# SCH_Solder_2025-04-30.net
KiCad netlist of a schematic drawn in EasyEDA
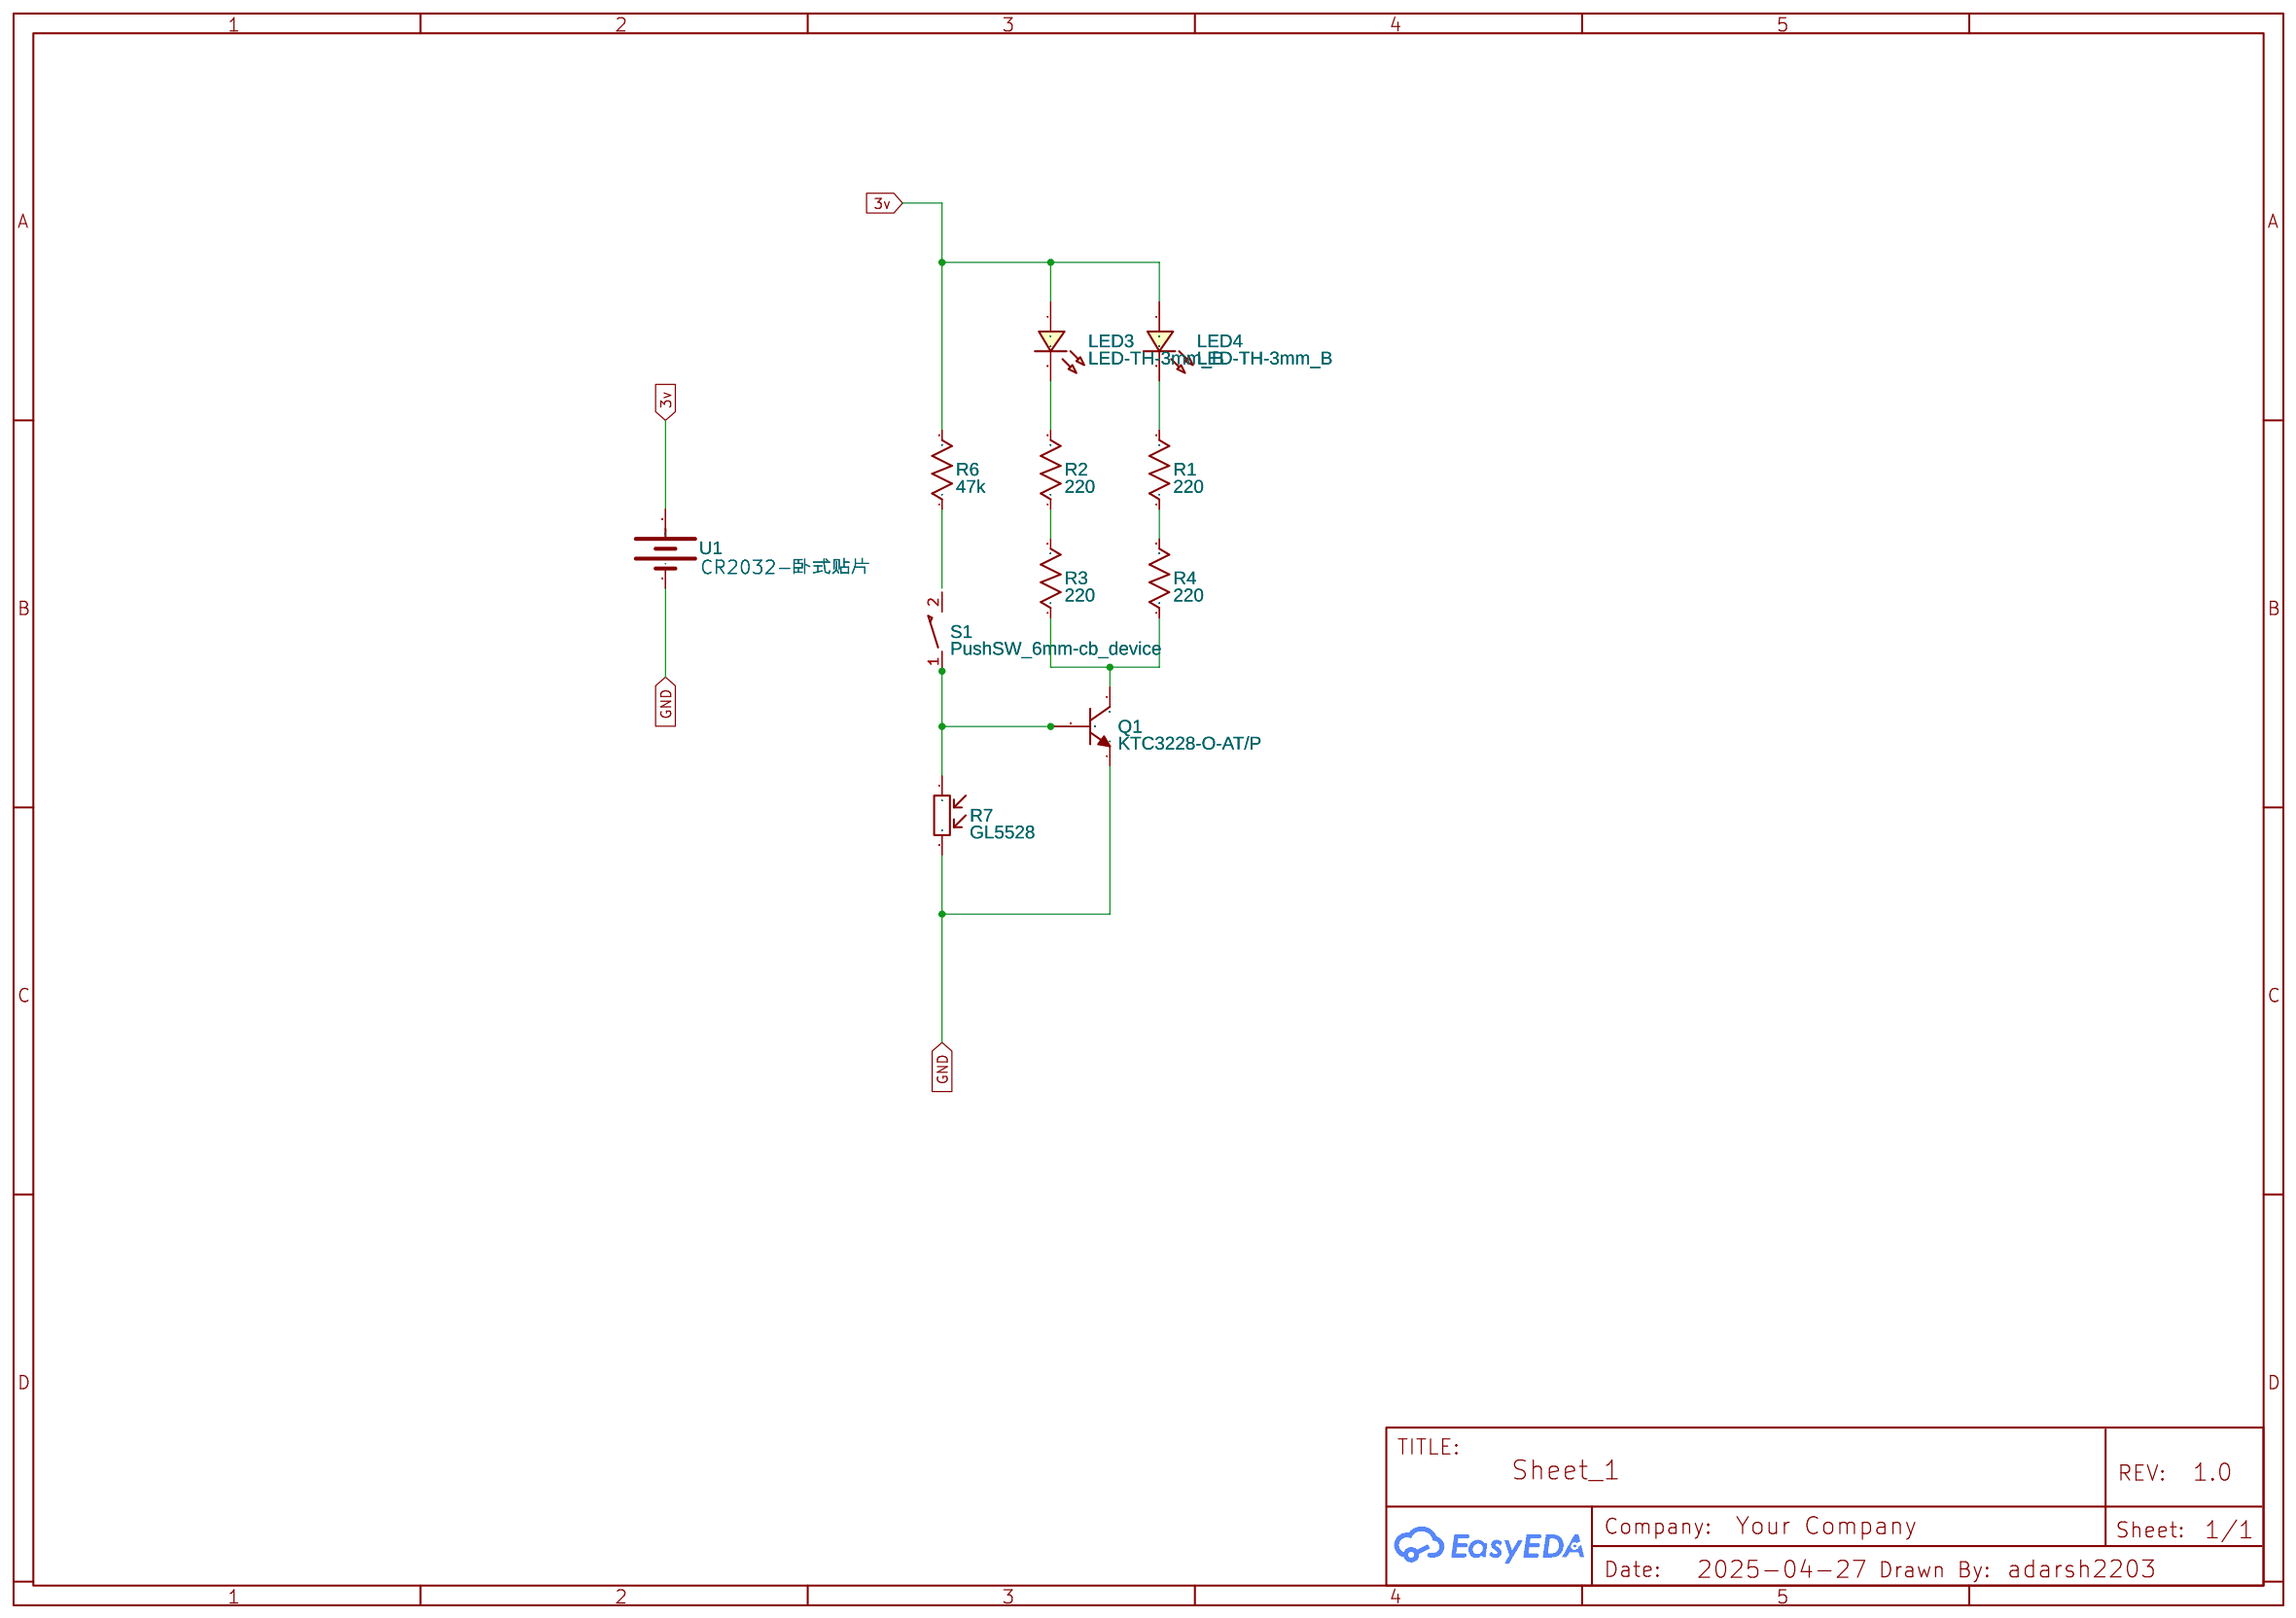
[diagram p0: schematic sheet]

(export (version "E")
  (design (tool "Eeschema 10.0.6"))
  (components
    (comp (ref "LED3")
      (value "LED-TH-3mm_B")
      (fields
        (field (name "Manufacturer Part") "204-10SUBC/S400-A4")
        (field (name "Manufacturer") "EVERLIGHT(台湾亿光)")
      )
      (libsource (lib "") (part "LED-TH-3mm_B"))
    )
    (comp (ref "LED4")
      (value "LED-TH-3mm_B")
      (fields
        (field (name "Manufacturer Part") "204-10SUBC/S400-A4")
        (field (name "Manufacturer") "EVERLIGHT(台湾亿光)")
      )
      (libsource (lib "") (part "LED-TH-3mm_B"))
    )
    (comp (ref "Q1")
      (value "KTC3228-O-AT/P")
      (fields (field (name "Manufacturer") "KEC"))
      (libsource (lib "") (part "KTC3228-O-AT/P"))
    )
    (comp (ref "R1") (value "220") (libsource (lib "") (part "R_AXIAL-0.3_US")))
    (comp (ref "R2") (value "220") (libsource (lib "") (part "R_AXIAL-0.3_US")))
    (comp (ref "R3") (value "220") (libsource (lib "") (part "R_AXIAL-0.3_US")))
    (comp (ref "R4") (value "220") (libsource (lib "") (part "R_AXIAL-0.3_US")))
    (comp (ref "R6") (value "47k") (libsource (lib "") (part "R_AXIAL-0.3_US")))
    (comp (ref "R7")
      (value "GL5528")
      (fields (field (name "Manufacturer") "森霸"))
      (libsource (lib "") (part "GL5528"))
    )
    (comp (ref "S1") (value "PushSW_6mm-cb_device") (libsource (lib "") (part "PushSW_6mm-cb_device")))
    (comp (ref "U1") (value "CR2032-卧式贴片") (libsource (lib "") (part "CR2032-卧式贴片")))
  )
  (nets
    (net (code "1") (name "3v") (class "Default")
      (node (ref "LED3") (pin "1") (pinfunction "1_1") (pintype "unspecified"))
      (node (ref "LED4") (pin "1") (pinfunction "1_1") (pintype "unspecified"))
      (node (ref "R6") (pin "2") (pinfunction "2_2") (pintype "unspecified"))
      (node (ref "U1") (pin "2") (pinfunction "+_2") (pintype "passive"))
    )
    (net (code "2") (name "GND") (class "Default")
      (node (ref "Q1") (pin "1") (pinfunction "E_1") (pintype "unspecified"))
      (node (ref "R7") (pin "2") (pinfunction "2_2") (pintype "input"))
      (node (ref "U1") (pin "1") (pinfunction "-_1") (pintype "passive"))
    )
    (net (code "3") (name "Net-(LED3-Pad2)") (class "Default")
      (node (ref "LED3") (pin "2") (pinfunction "2_2") (pintype "unspecified"))
      (node (ref "R2") (pin "2") (pinfunction "2_2") (pintype "unspecified"))
    )
    (net (code "4") (name "Net-(LED4-Pad2)") (class "Default")
      (node (ref "LED4") (pin "2") (pinfunction "2_2") (pintype "unspecified"))
      (node (ref "R1") (pin "2") (pinfunction "2_2") (pintype "unspecified"))
    )
    (net (code "5") (name "Net-(Q1-B)") (class "Default")
      (node (ref "Q1") (pin "3") (pinfunction "B_3") (pintype "unspecified"))
      (node (ref "R7") (pin "1") (pinfunction "1_1") (pintype "input"))
      (node (ref "S1") (pin "1") (pintype "input"))
    )
    (net (code "6") (name "Net-(Q1-C)") (class "Default")
      (node (ref "Q1") (pin "2") (pinfunction "C_2") (pintype "unspecified"))
      (node (ref "R3") (pin "1") (pinfunction "1_1") (pintype "unspecified"))
      (node (ref "R4") (pin "1") (pinfunction "1_1") (pintype "unspecified"))
    )
    (net (code "7") (name "Net-(R1-Pad1)") (class "Default")
      (node (ref "R1") (pin "1") (pinfunction "1_1") (pintype "unspecified"))
      (node (ref "R4") (pin "2") (pinfunction "2_2") (pintype "unspecified"))
    )
    (net (code "8") (name "Net-(R2-Pad1)") (class "Default")
      (node (ref "R2") (pin "1") (pinfunction "1_1") (pintype "unspecified"))
      (node (ref "R3") (pin "2") (pinfunction "2_2") (pintype "unspecified"))
    )
    (net (code "9") (name "unconnected-(R6-Pad1)") (class "Default")
      (node (ref "R6") (pin "1") (pinfunction "1_1") (pintype "unspecified"))
    )
    (net (code "10") (name "unconnected-(S1-Pad2)") (class "Default")
      (node (ref "S1") (pin "2") (pintype "input"))
    )
  )
)
